# Cup_and_Wash_v2.net
KiCad netlist of a schematic drawn in EAGLE
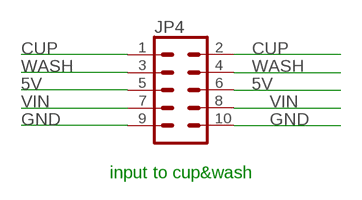
[diagram p0: schematic, sheet 1]
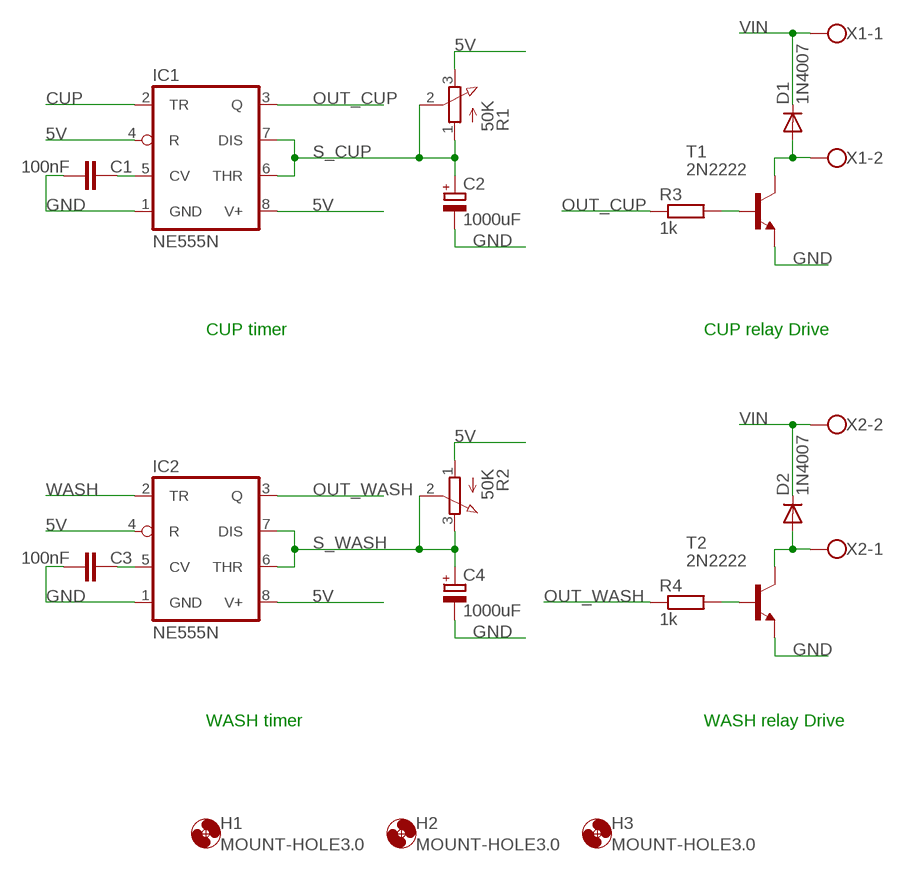
[diagram p1: schematic, sheet 2]

(export (version "E")
  (design (tool "Eeschema 10.0.6"))
  (components
    (comp (ref "C1")
      (value "100nF")
      (footprint "eagle-import:C050-025X075")
      (libsource (lib "eagle-import") (part "C-EU050-025X075"))
    )
    (comp (ref "C2")
      (value "1000uF")
      (footprint "eagle-import:E5-13")
      (libsource (lib "eagle-import") (part "CPOL-EUE5-13"))
    )
    (comp (ref "C3")
      (value "100nF")
      (footprint "eagle-import:C050-025X075")
      (libsource (lib "eagle-import") (part "C-EU050-025X075"))
    )
    (comp (ref "C4")
      (value "1000uF")
      (footprint "eagle-import:E5-13")
      (libsource (lib "eagle-import") (part "CPOL-EUE5-13"))
    )
    (comp (ref "D1")
      (value "1N4007")
      (footprint "eagle-import:DO41-10")
      (libsource (lib "eagle-import") (part "1N4004"))
    )
    (comp (ref "D2")
      (value "1N4007")
      (footprint "eagle-import:DO41-10")
      (libsource (lib "eagle-import") (part "1N4004"))
    )
    (comp (ref "H1")
      (value "MOUNT-HOLE3.0")
      (footprint "eagle-import:3,0")
      (libsource (lib "eagle-import") (part "MOUNT-HOLE3.0"))
    )
    (comp (ref "H2")
      (value "MOUNT-HOLE3.0")
      (footprint "eagle-import:3,0")
      (libsource (lib "eagle-import") (part "MOUNT-HOLE3.0"))
    )
    (comp (ref "H3")
      (value "MOUNT-HOLE3.0")
      (footprint "eagle-import:3,0")
      (libsource (lib "eagle-import") (part "MOUNT-HOLE3.0"))
    )
    (comp (ref "IC1")
      (value "NE555N")
      (footprint "eagle-import:DIL08-ROUND")
      (libsource (lib "eagle-import") (part "555NNE"))
    )
    (comp (ref "IC2")
      (value "NE555N")
      (footprint "eagle-import:DIL08-ROUND")
      (libsource (lib "eagle-import") (part "555NNE"))
    )
    (comp (ref "R1")
      (value "50K")
      (footprint "eagle-import:3RP_1610N")
      (libsource (lib "eagle-import") (part "3RP/1610N"))
    )
    (comp (ref "R2")
      (value "50K")
      (footprint "eagle-import:3RP_1610N")
      (libsource (lib "eagle-import") (part "3RP/1610N"))
    )
    (comp (ref "R3")
      (value "1k")
      (footprint "eagle-import:0207_10")
      (libsource (lib "eagle-import") (part "R-EU_0207/10"))
    )
    (comp (ref "R4")
      (value "1k")
      (footprint "eagle-import:0207_10")
      (libsource (lib "eagle-import") (part "R-EU_0207/10"))
    )
    (comp (ref "T1")
      (value "2N2222")
      (footprint "eagle-import:TO92-EBC-OVAL")
      (libsource (lib "eagle-import") (part "2N2222"))
    )
    (comp (ref "T2")
      (value "2N2222")
      (footprint "eagle-import:TO92-EBC-OVAL")
      (libsource (lib "eagle-import") (part "2N2222"))
    )
    (comp (ref "X1")
      (value "W237-102")
      (footprint "eagle-import:W237-102")
      (fields (field (name "MPN") "237-102"))
      (libsource (lib "eagle-import") (part "W237-102"))
    )
    (comp (ref "X2")
      (value "W237-102")
      (footprint "eagle-import:W237-102")
      (fields (field (name "MPN") "237-102"))
      (libsource (lib "eagle-import") (part "W237-102"))
    )
    (comp (ref "JP4")
      (value "CONN_05X2PTH")
      (footprint "eagle-import:2X5")
      (libsource (lib "eagle-import") (part "CONN_05X2PTH"))
    )
  )
  (nets
    (net (code "1") (name "5V") (class "Default")
      (node (ref "IC1") (pin "4") (pinfunction "R_4") (pintype "input"))
      (node (ref "IC1") (pin "8") (pinfunction "V+_8") (pintype "power_in"))
      (node (ref "IC2") (pin "4") (pinfunction "R_4") (pintype "input"))
      (node (ref "IC2") (pin "8") (pinfunction "V+_8") (pintype "power_in"))
      (node (ref "JP4") (pin "5") (pinfunction "5_5") (pintype "passive"))
      (node (ref "JP4") (pin "6") (pinfunction "6_6") (pintype "passive"))
      (node (ref "R1") (pin "3") (pinfunction "E_3") (pintype "passive"))
      (node (ref "R2") (pin "1") (pinfunction "A_1") (pintype "passive"))
    )
    (net (code "2") (name "CUP") (class "Default")
      (node (ref "IC1") (pin "2") (pinfunction "TR_2") (pintype "input"))
      (node (ref "JP4") (pin "1") (pinfunction "1_1") (pintype "passive"))
      (node (ref "JP4") (pin "2") (pinfunction "2_2") (pintype "passive"))
    )
    (net (code "3") (name "GND") (class "Default")
      (node (ref "C1") (pin "2") (pinfunction "2_2") (pintype "passive"))
      (node (ref "C2") (pin "-") (pinfunction "-_-") (pintype "passive"))
      (node (ref "C3") (pin "2") (pinfunction "2_2") (pintype "passive"))
      (node (ref "C4") (pin "-") (pinfunction "-_-") (pintype "passive"))
      (node (ref "IC1") (pin "1") (pinfunction "GND_1") (pintype "power_in"))
      (node (ref "IC2") (pin "1") (pinfunction "GND_1") (pintype "power_in"))
      (node (ref "JP4") (pin "10") (pinfunction "10_10") (pintype "passive"))
      (node (ref "JP4") (pin "9") (pinfunction "9_9") (pintype "passive"))
      (node (ref "T1") (pin "E") (pinfunction "E_E") (pintype "passive"))
      (node (ref "T2") (pin "E") (pinfunction "E_E") (pintype "passive"))
    )
    (net (code "4") (name "Net-(IC1-CV)") (class "Default")
      (node (ref "C1") (pin "1") (pinfunction "1_1") (pintype "passive"))
      (node (ref "IC1") (pin "5") (pinfunction "CV_5") (pintype "input"))
    )
    (net (code "5") (name "Net-(IC2-CV)") (class "Default")
      (node (ref "C3") (pin "1") (pinfunction "1_1") (pintype "passive"))
      (node (ref "IC2") (pin "5") (pinfunction "CV_5") (pintype "input"))
    )
    (net (code "6") (name "Net-(R3-Pad2)") (class "Default")
      (node (ref "R3") (pin "2") (pinfunction "2_2") (pintype "passive"))
      (node (ref "T1") (pin "B") (pinfunction "B_B") (pintype "passive"))
    )
    (net (code "7") (name "Net-(R4-Pad2)") (class "Default")
      (node (ref "R4") (pin "2") (pinfunction "2_2") (pintype "passive"))
      (node (ref "T2") (pin "B") (pinfunction "B_B") (pintype "passive"))
    )
    (net (code "8") (name "Net-(X1B-KL)") (class "Default")
      (node (ref "D1") (pin "A") (pinfunction "A_A") (pintype "passive"))
      (node (ref "T1") (pin "C") (pinfunction "C_C") (pintype "passive"))
      (node (ref "X1") (pin "2") (pinfunction "KL_2") (pintype "passive"))
    )
    (net (code "9") (name "Net-(X2A-KL)") (class "Default")
      (node (ref "D2") (pin "A") (pinfunction "A_A") (pintype "passive"))
      (node (ref "T2") (pin "C") (pinfunction "C_C") (pintype "passive"))
      (node (ref "X2") (pin "1") (pinfunction "KL_1") (pintype "passive"))
    )
    (net (code "10") (name "OUT_CUP") (class "Default")
      (node (ref "IC1") (pin "3") (pinfunction "Q_3") (pintype "output"))
      (node (ref "R3") (pin "1") (pinfunction "1_1") (pintype "passive"))
    )
    (net (code "11") (name "OUT_WASH") (class "Default")
      (node (ref "IC2") (pin "3") (pinfunction "Q_3") (pintype "output"))
      (node (ref "R4") (pin "1") (pinfunction "1_1") (pintype "passive"))
    )
    (net (code "12") (name "S_CUP") (class "Default")
      (node (ref "C2") (pin "+") (pinfunction "+_+") (pintype "passive"))
      (node (ref "IC1") (pin "6") (pinfunction "THR_6") (pintype "input"))
      (node (ref "IC1") (pin "7") (pinfunction "DIS_7") (pintype "input"))
      (node (ref "R1") (pin "1") (pinfunction "A_1") (pintype "passive"))
      (node (ref "R1") (pin "2") (pinfunction "S_2") (pintype "passive"))
    )
    (net (code "13") (name "S_WASH") (class "Default")
      (node (ref "C4") (pin "+") (pinfunction "+_+") (pintype "passive"))
      (node (ref "IC2") (pin "6") (pinfunction "THR_6") (pintype "input"))
      (node (ref "IC2") (pin "7") (pinfunction "DIS_7") (pintype "input"))
      (node (ref "R2") (pin "2") (pinfunction "S_2") (pintype "passive"))
      (node (ref "R2") (pin "3") (pinfunction "E_3") (pintype "passive"))
    )
    (net (code "14") (name "VIN") (class "Default")
      (node (ref "D1") (pin "C") (pinfunction "C_C") (pintype "passive"))
      (node (ref "D2") (pin "C") (pinfunction "C_C") (pintype "passive"))
      (node (ref "JP4") (pin "7") (pinfunction "7_7") (pintype "passive"))
      (node (ref "JP4") (pin "8") (pinfunction "8_8") (pintype "passive"))
      (node (ref "X1") (pin "1") (pinfunction "KL_1") (pintype "passive"))
      (node (ref "X2") (pin "2") (pinfunction "KL_2") (pintype "passive"))
    )
    (net (code "15") (name "WASH") (class "Default")
      (node (ref "IC2") (pin "2") (pinfunction "TR_2") (pintype "input"))
      (node (ref "JP4") (pin "3") (pinfunction "3_3") (pintype "passive"))
      (node (ref "JP4") (pin "4") (pinfunction "4_4") (pintype "passive"))
    )
  )
)
